# relaissteuerung.net
KiCad netlist of a schematic drawn in EAGLE
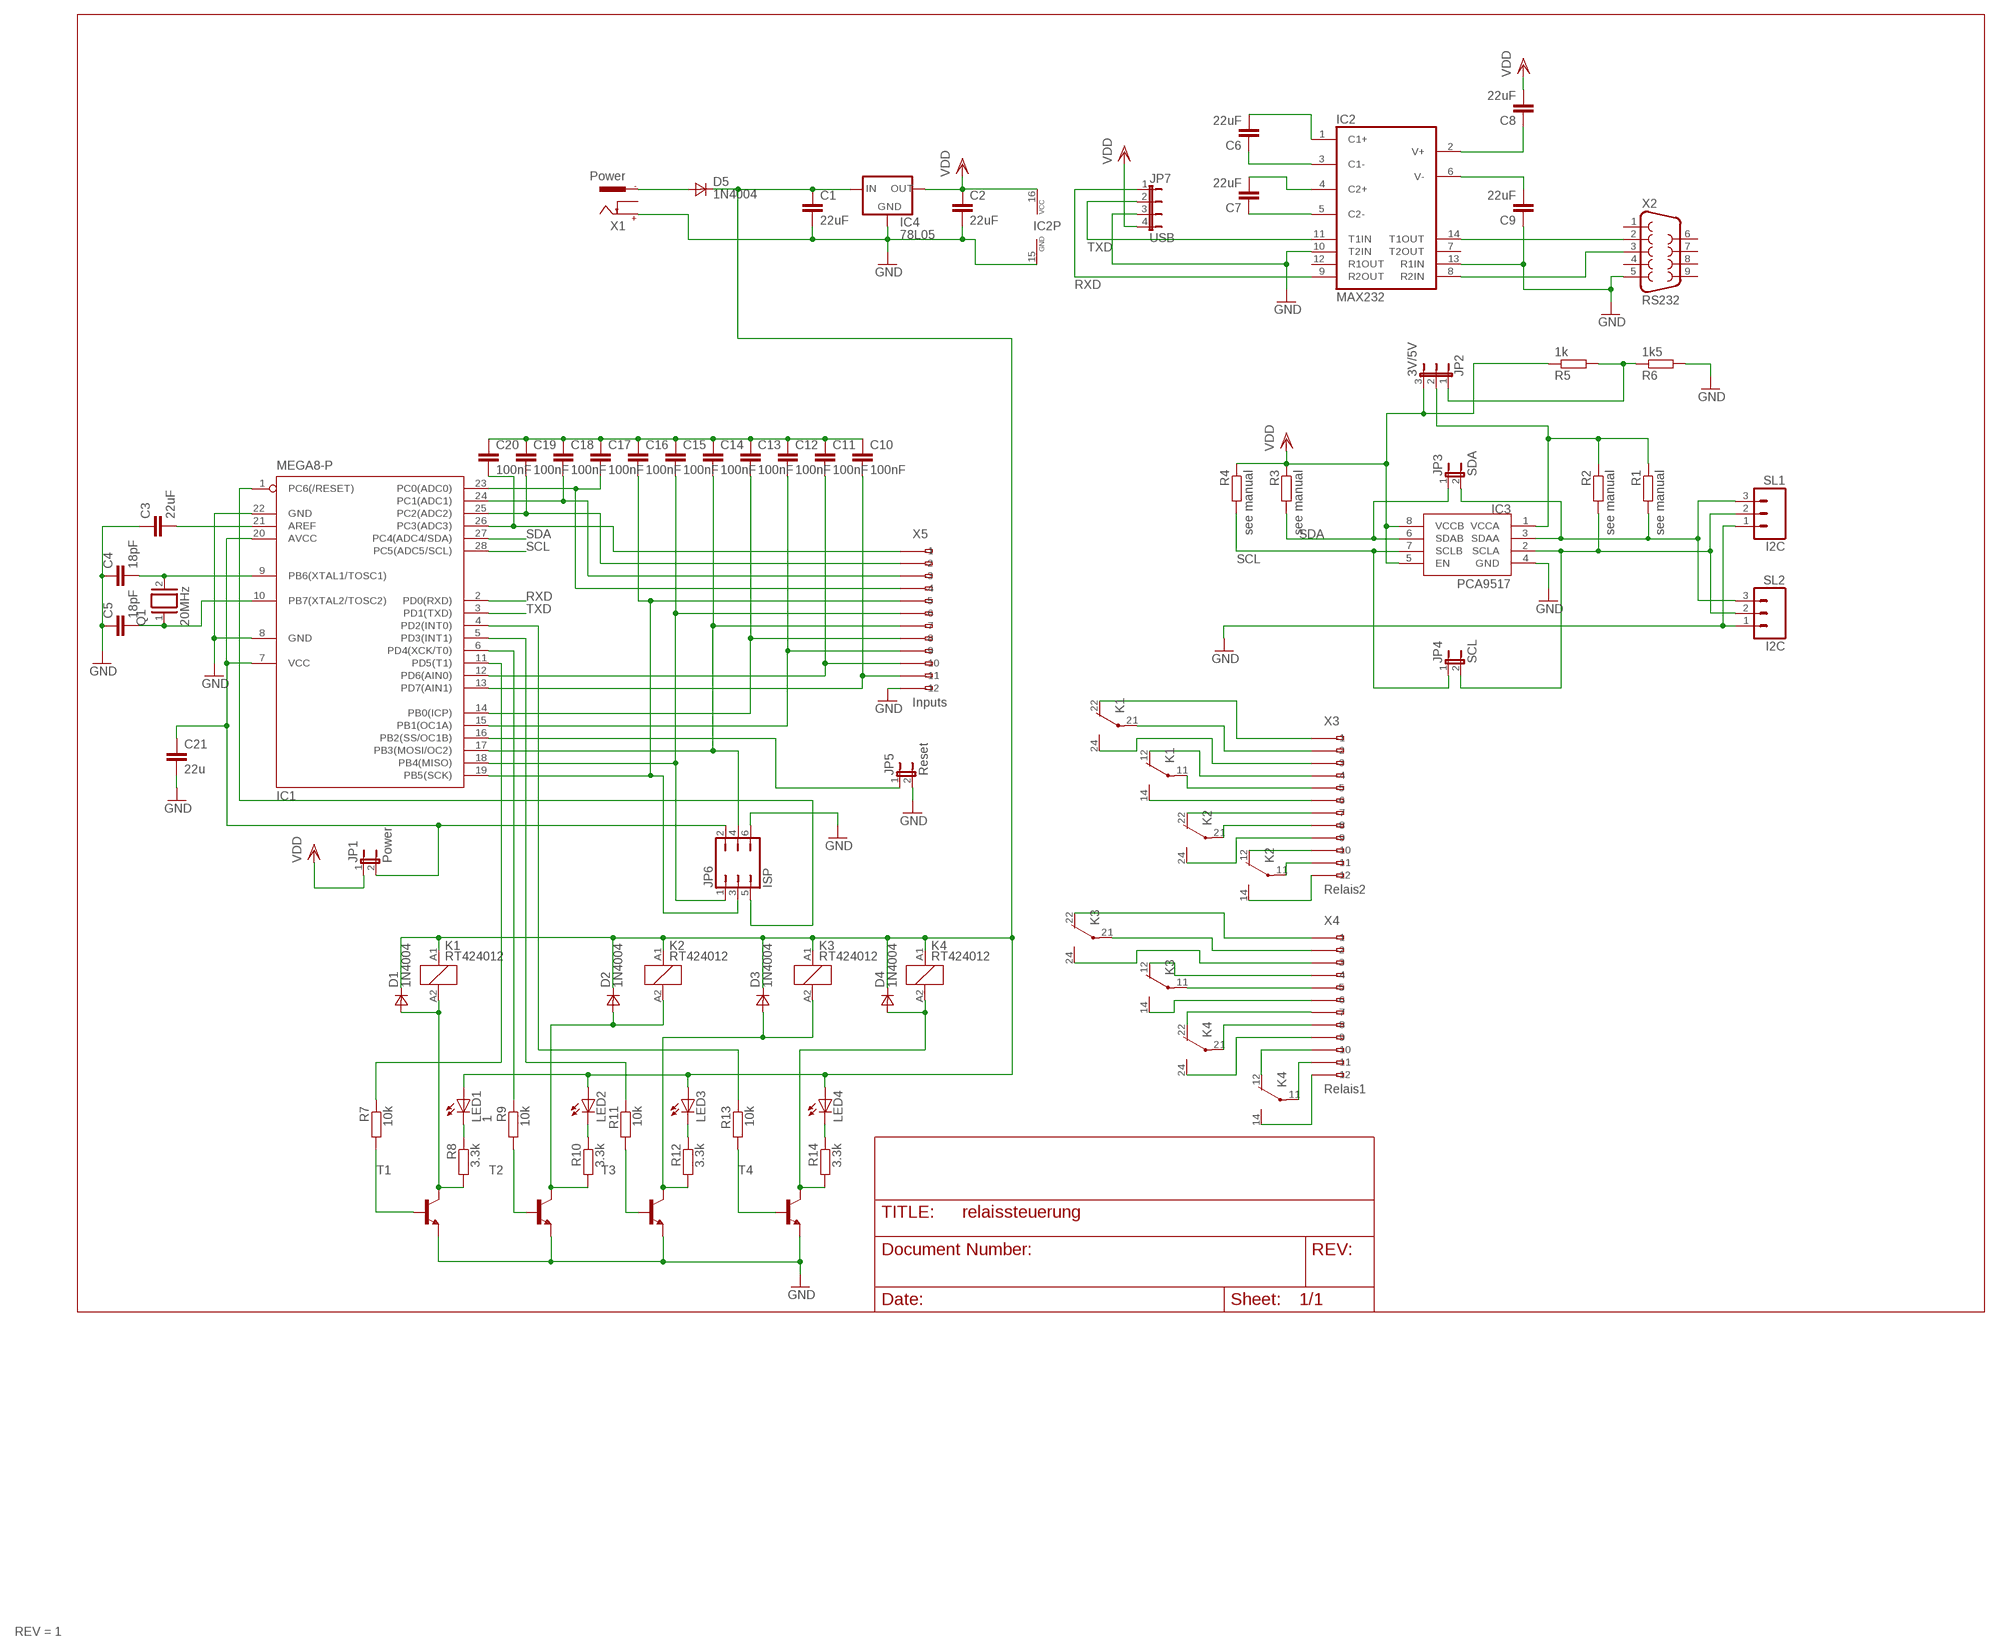
[diagram p0: schematic, sheet 1]

(export (version "E")
  (design (tool "Eeschema 10.0.6"))
  (components
    (comp (ref "C1")
      (value "22uF")
      (footprint "eagle-import:C1206")
      (libsource (lib "eagle-import") (part "resistor_C-EUC1206"))
    )
    (comp (ref "C2")
      (value "22uF")
      (footprint "eagle-import:C1206")
      (libsource (lib "eagle-import") (part "resistor_C-EUC1206"))
    )
    (comp (ref "C3")
      (value "22uF")
      (footprint "eagle-import:C1206")
      (libsource (lib "eagle-import") (part "resistor_C-EUC1206"))
    )
    (comp (ref "C4")
      (value "18pF")
      (footprint "eagle-import:C050-025X075")
      (libsource (lib "eagle-import") (part "resistor_C-EU050-025X075"))
    )
    (comp (ref "C5")
      (value "18pF")
      (footprint "eagle-import:C050-025X075")
      (libsource (lib "eagle-import") (part "resistor_C-EU050-025X075"))
    )
    (comp (ref "C6")
      (value "22uF")
      (footprint "eagle-import:C1206")
      (libsource (lib "eagle-import") (part "C-EUC1206"))
    )
    (comp (ref "C7")
      (value "22uF")
      (footprint "eagle-import:C1206")
      (libsource (lib "eagle-import") (part "C-EUC1206"))
    )
    (comp (ref "C8")
      (value "22uF")
      (footprint "eagle-import:C1206")
      (libsource (lib "eagle-import") (part "C-EUC1206"))
    )
    (comp (ref "C9")
      (value "22uF")
      (footprint "eagle-import:C1206")
      (libsource (lib "eagle-import") (part "C-EUC1206"))
    )
    (comp (ref "C10")
      (value "100nF")
      (footprint "eagle-import:C1206")
      (libsource (lib "eagle-import") (part "resistor_C-EUC1206"))
    )
    (comp (ref "C11")
      (value "100nF")
      (footprint "eagle-import:C1206")
      (libsource (lib "eagle-import") (part "resistor_C-EUC1206"))
    )
    (comp (ref "C12")
      (value "100nF")
      (footprint "eagle-import:C1206")
      (libsource (lib "eagle-import") (part "resistor_C-EUC1206"))
    )
    (comp (ref "C13")
      (value "100nF")
      (footprint "eagle-import:C1206")
      (libsource (lib "eagle-import") (part "resistor_C-EUC1206"))
    )
    (comp (ref "C14")
      (value "100nF")
      (footprint "eagle-import:C1206")
      (libsource (lib "eagle-import") (part "resistor_C-EUC1206"))
    )
    (comp (ref "C15")
      (value "100nF")
      (footprint "eagle-import:C1206")
      (libsource (lib "eagle-import") (part "resistor_C-EUC1206"))
    )
    (comp (ref "C16")
      (value "100nF")
      (footprint "eagle-import:C1206")
      (libsource (lib "eagle-import") (part "resistor_C-EUC1206"))
    )
    (comp (ref "C17")
      (value "100nF")
      (footprint "eagle-import:C1206")
      (libsource (lib "eagle-import") (part "resistor_C-EUC1206"))
    )
    (comp (ref "C18")
      (value "100nF")
      (footprint "eagle-import:C1206")
      (libsource (lib "eagle-import") (part "resistor_C-EUC1206"))
    )
    (comp (ref "C19")
      (value "100nF")
      (footprint "eagle-import:C1206")
      (libsource (lib "eagle-import") (part "resistor_C-EUC1206"))
    )
    (comp (ref "C20")
      (value "100nF")
      (footprint "eagle-import:C1206")
      (libsource (lib "eagle-import") (part "resistor_C-EUC1206"))
    )
    (comp (ref "C21")
      (value "22u")
      (footprint "eagle-import:C1206")
      (libsource (lib "eagle-import") (part "resistor_C-EUC1206"))
    )
    (comp (ref "D1")
      (value "1N4004")
      (footprint "eagle-import:E2LINE")
      (libsource (lib "eagle-import") (part "D_E2L"))
    )
    (comp (ref "D2")
      (value "1N4004")
      (footprint "eagle-import:E2LINE")
      (libsource (lib "eagle-import") (part "D_E2L"))
    )
    (comp (ref "D3")
      (value "1N4004")
      (footprint "eagle-import:E2LINE")
      (libsource (lib "eagle-import") (part "D_E2L"))
    )
    (comp (ref "D4")
      (value "1N4004")
      (footprint "eagle-import:E2LINE")
      (libsource (lib "eagle-import") (part "D_E2L"))
    )
    (comp (ref "D5")
      (value "1N4004")
      (footprint "eagle-import:E2LINE")
      (libsource (lib "eagle-import") (part "D_E2L"))
    )
    (comp (ref "IC1")
      (value "MEGA8-P")
      (footprint "eagle-import:DIL28-3")
      (libsource (lib "eagle-import") (part "MEGA8-P"))
    )
    (comp (ref "IC2")
      (value "MAX232")
      (footprint "eagle-import:DIL16")
      (fields (field (name "MF") "MAXIM") (field (name "MPN") "MAX232ACPE+"))
      (libsource (lib "eagle-import") (part "MAX232"))
    )
    (comp (ref "IC3")
      (value "PCA9517")
      (footprint "eagle-import:SO-08")
      (libsource (lib "eagle-import") (part "PCA9517"))
    )
    (comp (ref "IC4")
      (value "78L05")
      (footprint "eagle-import:78LXX")
      (libsource (lib "eagle-import") (part "78LXX"))
    )
    (comp (ref "JP1")
      (value "Power")
      (footprint "eagle-import:JP1")
      (libsource (lib "eagle-import") (part "JP1E"))
    )
    (comp (ref "JP2")
      (value "3V/5V")
      (footprint "eagle-import:JP2")
      (libsource (lib "eagle-import") (part "JP2E"))
    )
    (comp (ref "JP3")
      (value "SDA")
      (footprint "eagle-import:JP1")
      (libsource (lib "eagle-import") (part "JP1E"))
    )
    (comp (ref "JP4")
      (value "SCL")
      (footprint "eagle-import:JP1")
      (libsource (lib "eagle-import") (part "JP1E"))
    )
    (comp (ref "JP5")
      (value "Reset")
      (footprint "eagle-import:JP1")
      (libsource (lib "eagle-import") (part "JP1E"))
    )
    (comp (ref "JP6")
      (value "ISP")
      (footprint "eagle-import:JP3Q")
      (libsource (lib "eagle-import") (part "JP3Q"))
    )
    (comp (ref "JP7")
      (value "USB")
      (footprint "eagle-import:JP4")
      (libsource (lib "eagle-import") (part "JP4E"))
    )
    (comp (ref "K1")
      (value "RT424012")
      (footprint "eagle-import:RT2C_O")
      (libsource (lib "eagle-import") (part "RT42?4012"))
    )
    (comp (ref "K2")
      (value "RT424012")
      (footprint "eagle-import:RT2C_O")
      (libsource (lib "eagle-import") (part "RT42?4012"))
    )
    (comp (ref "K3")
      (value "RT424012")
      (footprint "eagle-import:RT2C_O")
      (libsource (lib "eagle-import") (part "RT42?4012"))
    )
    (comp (ref "K4")
      (value "RT424012")
      (footprint "eagle-import:RT2C_O")
      (libsource (lib "eagle-import") (part "RT42?4012"))
    )
    (comp (ref "LED1")
      (value "1")
      (footprint "eagle-import:LED3MM")
      (libsource (lib "eagle-import") (part "LED3MM"))
    )
    (comp (ref "LED2")
      (value "LED3MM")
      (footprint "eagle-import:LED3MM")
      (libsource (lib "eagle-import") (part "LED3MM"))
    )
    (comp (ref "LED3")
      (value "LED3MM")
      (footprint "eagle-import:LED3MM")
      (libsource (lib "eagle-import") (part "LED3MM"))
    )
    (comp (ref "LED4")
      (value "LED3MM")
      (footprint "eagle-import:LED3MM")
      (libsource (lib "eagle-import") (part "LED3MM"))
    )
    (comp (ref "Q1")
      (value "20MHz")
      (footprint "eagle-import:QS")
      (libsource (lib "eagle-import") (part "XTAL/S"))
    )
    (comp (ref "R1")
      (value "see manual")
      (footprint "eagle-import:R1206")
      (libsource (lib "eagle-import") (part "resistor_R-EU_R1206"))
    )
    (comp (ref "R2")
      (value "see manual")
      (footprint "eagle-import:R1206")
      (libsource (lib "eagle-import") (part "resistor_R-EU_R1206"))
    )
    (comp (ref "R3")
      (value "see manual")
      (footprint "eagle-import:R1206")
      (libsource (lib "eagle-import") (part "resistor_R-EU_R1206"))
    )
    (comp (ref "R4")
      (value "see manual")
      (footprint "eagle-import:R1206")
      (libsource (lib "eagle-import") (part "resistor_R-EU_R1206"))
    )
    (comp (ref "R5")
      (value "1k")
      (footprint "eagle-import:R1206")
      (libsource (lib "eagle-import") (part "resistor_R-EU_R1206"))
    )
    (comp (ref "R6")
      (value "1k5")
      (footprint "eagle-import:R1206")
      (libsource (lib "eagle-import") (part "resistor_R-EU_R1206"))
    )
    (comp (ref "R7")
      (value "10k")
      (footprint "eagle-import:R1206")
      (libsource (lib "eagle-import") (part "R-EU_R1206"))
    )
    (comp (ref "R8")
      (value "3.3k")
      (footprint "eagle-import:R1206")
      (libsource (lib "eagle-import") (part "R-EU_R1206"))
    )
    (comp (ref "R9")
      (value "10k")
      (footprint "eagle-import:M1206")
      (libsource (lib "eagle-import") (part "R-EU_M1206"))
    )
    (comp (ref "R10")
      (value "3.3k")
      (footprint "eagle-import:R1206")
      (libsource (lib "eagle-import") (part "R-EU_R1206"))
    )
    (comp (ref "R11")
      (value "10k")
      (footprint "eagle-import:R1206")
      (libsource (lib "eagle-import") (part "R-EU_R1206"))
    )
    (comp (ref "R12")
      (value "3.3k")
      (footprint "eagle-import:R1206")
      (libsource (lib "eagle-import") (part "R-EU_R1206"))
    )
    (comp (ref "R13")
      (value "10k")
      (footprint "eagle-import:M1206")
      (libsource (lib "eagle-import") (part "R-EU_M1206"))
    )
    (comp (ref "R14")
      (value "3.3k")
      (footprint "eagle-import:R1206")
      (libsource (lib "eagle-import") (part "R-EU_R1206"))
    )
    (comp (ref "SL1")
      (value "I2C")
      (footprint "eagle-import:03P")
      (libsource (lib "eagle-import") (part "M03"))
    )
    (comp (ref "SL2")
      (value "I2C")
      (footprint "eagle-import:03P")
      (libsource (lib "eagle-import") (part "M03"))
    )
    (comp (ref "T1")
      (value "BC817-16-NPN-SOT23-BEC")
      (footprint "eagle-import:SOT23-BEC")
      (libsource (lib "eagle-import") (part "-NPN-SOT23-BECBC817-16"))
    )
    (comp (ref "T2")
      (value "BC817-16-NPN-SOT23-BEC")
      (footprint "eagle-import:SOT23-BEC")
      (libsource (lib "eagle-import") (part "-NPN-SOT23-BECBC817-16"))
    )
    (comp (ref "T3")
      (value "BC817-16-NPN-SOT23-BEC")
      (footprint "eagle-import:SOT23-BEC")
      (libsource (lib "eagle-import") (part "-NPN-SOT23-BECBC817-16"))
    )
    (comp (ref "T4")
      (value "BC817-16-NPN-SOT23-BEC")
      (footprint "eagle-import:SOT23-BEC")
      (libsource (lib "eagle-import") (part "-NPN-SOT23-BECBC817-16"))
    )
    (comp (ref "X1")
      (value "Power")
      (footprint "eagle-import:737992-5")
      (libsource (lib "eagle-import") (part "737992-55"))
    )
    (comp (ref "X2")
      (value "RS232")
      (footprint "eagle-import:F09H")
      (libsource (lib "eagle-import") (part "F09H"))
    )
    (comp (ref "X3")
      (value "Relais2")
      (footprint "eagle-import:233-512")
      (fields (field (name "MF") "Wago Corporation") (field (name "MPN") "0233-0512"))
      (libsource (lib "eagle-import") (part "233-512"))
    )
    (comp (ref "X4")
      (value "Relais1")
      (footprint "eagle-import:233-512")
      (fields (field (name "MF") "Wago Corporation") (field (name "MPN") "0233-0512"))
      (libsource (lib "eagle-import") (part "233-512"))
    )
    (comp (ref "X5")
      (value "Inputs")
      (footprint "eagle-import:233-512")
      (fields (field (name "MF") "Wago Corporation") (field (name "MPN") "0233-0512"))
      (libsource (lib "eagle-import") (part "233-512"))
    )
  )
  (nets
    (net (code "1") (name "/RXD") (class "Default")
      (node (ref "IC1") (pin "2") (pinfunction "PD0(RXD)_2") (pintype "bidirectional"))
      (node (ref "IC2") (pin "9") (pinfunction "R2OUT_9") (pintype "output"))
      (node (ref "JP7") (pin "1") (pinfunction "1_1") (pintype "passive"))
    )
    (net (code "2") (name "/SCL") (class "Default")
      (node (ref "IC1") (pin "28") (pinfunction "PC5(ADC5/SCL)_28") (pintype "bidirectional"))
      (node (ref "IC3") (pin "7") (pinfunction "SCLB_7") (pintype "bidirectional"))
      (node (ref "JP4") (pin "1") (pinfunction "1_1") (pintype "passive"))
      (node (ref "R4") (pin "2") (pinfunction "2_2") (pintype "passive"))
    )
    (net (code "3") (name "/SDA") (class "Default")
      (node (ref "IC1") (pin "27") (pinfunction "PC4(ADC4/SDA)_27") (pintype "bidirectional"))
      (node (ref "IC3") (pin "6") (pinfunction "SDAB_6") (pintype "bidirectional"))
      (node (ref "JP3") (pin "1") (pinfunction "1_1") (pintype "passive"))
      (node (ref "R3") (pin "2") (pinfunction "2_2") (pintype "passive"))
    )
    (net (code "4") (name "/TXD") (class "Default")
      (node (ref "IC1") (pin "3") (pinfunction "PD1(TXD)_3") (pintype "bidirectional"))
      (node (ref "IC2") (pin "11") (pinfunction "T1IN_11") (pintype "input"))
      (node (ref "JP7") (pin "2") (pinfunction "2_2") (pintype "passive"))
    )
    (net (code "5") (name "GND") (class "Default")
      (node (ref "C1") (pin "2") (pinfunction "2_2") (pintype "passive"))
      (node (ref "C2") (pin "2") (pinfunction "2_2") (pintype "passive"))
      (node (ref "C21") (pin "2") (pinfunction "2_2") (pintype "passive"))
      (node (ref "C3") (pin "1") (pinfunction "1_1") (pintype "passive"))
      (node (ref "C4") (pin "1") (pinfunction "1_1") (pintype "passive"))
      (node (ref "C5") (pin "1") (pinfunction "1_1") (pintype "passive"))
      (node (ref "C9") (pin "1") (pinfunction "1_1") (pintype "passive"))
      (node (ref "IC1") (pin "22") (pinfunction "GND_22") (pintype "power_in"))
      (node (ref "IC1") (pin "8") (pinfunction "GND_8") (pintype "power_in"))
      (node (ref "IC2") (pin "10") (pinfunction "T2IN_10") (pintype "input"))
      (node (ref "IC2") (pin "13") (pinfunction "R1IN_13") (pintype "input"))
      (node (ref "IC2") (pin "15") (pinfunction "GND_15") (pintype "power_in"))
      (node (ref "IC3") (pin "4") (pinfunction "GND_4") (pintype "bidirectional"))
      (node (ref "IC4") (pin "GND") (pinfunction "GND_GND") (pintype "input"))
      (node (ref "JP5") (pin "2") (pinfunction "2_2") (pintype "passive"))
      (node (ref "JP6") (pin "6") (pinfunction "6_6") (pintype "passive"))
      (node (ref "JP7") (pin "3") (pinfunction "3_3") (pintype "passive"))
      (node (ref "R6") (pin "2") (pinfunction "2_2") (pintype "passive"))
      (node (ref "SL1") (pin "1") (pinfunction "1_1") (pintype "passive"))
      (node (ref "SL2") (pin "1") (pinfunction "1_1") (pintype "passive"))
      (node (ref "T1") (pin "E") (pinfunction "E_E") (pintype "passive"))
      (node (ref "T2") (pin "E") (pinfunction "E_E") (pintype "passive"))
      (node (ref "T3") (pin "E") (pinfunction "E_E") (pintype "passive"))
      (node (ref "T4") (pin "E") (pinfunction "E_E") (pintype "passive"))
      (node (ref "X1") (pin "+") (pinfunction "+_+") (pintype "passive"))
      (node (ref "X2") (pin "5") (pinfunction "5_5") (pintype "passive"))
      (node (ref "X5") (pin "A12") (pinfunction "-12_A12") (pintype "passive"))
    )
    (net (code "6") (name "Net-(C10-Pad1)") (class "Default")
      (node (ref "C10") (pin "1") (pinfunction "1_1") (pintype "passive"))
      (node (ref "C11") (pin "1") (pinfunction "1_1") (pintype "passive"))
      (node (ref "C12") (pin "1") (pinfunction "1_1") (pintype "passive"))
      (node (ref "C13") (pin "1") (pinfunction "1_1") (pintype "passive"))
      (node (ref "C14") (pin "1") (pinfunction "1_1") (pintype "passive"))
      (node (ref "C15") (pin "1") (pinfunction "1_1") (pintype "passive"))
      (node (ref "C16") (pin "1") (pinfunction "1_1") (pintype "passive"))
      (node (ref "C17") (pin "1") (pinfunction "1_1") (pintype "passive"))
      (node (ref "C18") (pin "1") (pinfunction "1_1") (pintype "passive"))
      (node (ref "C19") (pin "1") (pinfunction "1_1") (pintype "passive"))
      (node (ref "C20") (pin "1") (pinfunction "1_1") (pintype "passive"))
    )
    (net (code "7") (name "Net-(D1-A)") (class "Default")
      (node (ref "D1") (pin "2") (pinfunction "A_2") (pintype "passive"))
      (node (ref "K1") (pin "A2") (pinfunction "2_A2") (pintype "passive"))
      (node (ref "R8") (pin "2") (pinfunction "2_2") (pintype "passive"))
      (node (ref "T1") (pin "C") (pinfunction "C_C") (pintype "passive"))
    )
    (net (code "8") (name "Net-(D1-C)") (class "Default")
      (node (ref "C1") (pin "1") (pinfunction "1_1") (pintype "passive"))
      (node (ref "D1") (pin "1") (pinfunction "C_1") (pintype "passive"))
      (node (ref "D2") (pin "1") (pinfunction "C_1") (pintype "passive"))
      (node (ref "D3") (pin "1") (pinfunction "C_1") (pintype "passive"))
      (node (ref "D4") (pin "1") (pinfunction "C_1") (pintype "passive"))
      (node (ref "D5") (pin "1") (pinfunction "C_1") (pintype "passive"))
      (node (ref "IC4") (pin "IN") (pinfunction "IN_IN") (pintype "input"))
      (node (ref "K1") (pin "A1") (pinfunction "1_A1") (pintype "passive"))
      (node (ref "K2") (pin "A1") (pinfunction "1_A1") (pintype "passive"))
      (node (ref "K3") (pin "A1") (pinfunction "1_A1") (pintype "passive"))
      (node (ref "K4") (pin "A1") (pinfunction "1_A1") (pintype "passive"))
      (node (ref "LED1") (pin "A") (pinfunction "A_A") (pintype "passive"))
      (node (ref "LED2") (pin "A") (pinfunction "A_A") (pintype "passive"))
      (node (ref "LED3") (pin "A") (pinfunction "A_A") (pintype "passive"))
      (node (ref "LED4") (pin "A") (pinfunction "A_A") (pintype "passive"))
    )
    (net (code "9") (name "Net-(D2-A)") (class "Default")
      (node (ref "D2") (pin "2") (pinfunction "A_2") (pintype "passive"))
      (node (ref "K2") (pin "A2") (pinfunction "2_A2") (pintype "passive"))
      (node (ref "R10") (pin "2") (pinfunction "2_2") (pintype "passive"))
      (node (ref "T2") (pin "C") (pinfunction "C_C") (pintype "passive"))
    )
    (net (code "10") (name "Net-(D3-A)") (class "Default")
      (node (ref "D3") (pin "2") (pinfunction "A_2") (pintype "passive"))
      (node (ref "K3") (pin "A2") (pinfunction "2_A2") (pintype "passive"))
      (node (ref "R12") (pin "2") (pinfunction "2_2") (pintype "passive"))
      (node (ref "T3") (pin "C") (pinfunction "C_C") (pintype "passive"))
    )
    (net (code "11") (name "Net-(D4-A)") (class "Default")
      (node (ref "D4") (pin "2") (pinfunction "A_2") (pintype "passive"))
      (node (ref "K4") (pin "A2") (pinfunction "2_A2") (pintype "passive"))
      (node (ref "R14") (pin "2") (pinfunction "2_2") (pintype "passive"))
      (node (ref "T4") (pin "C") (pinfunction "C_C") (pintype "passive"))
    )
    (net (code "12") (name "Net-(D5-A)") (class "Default")
      (node (ref "D5") (pin "2") (pinfunction "A_2") (pintype "passive"))
      (node (ref "X1") (pin "-1") (pinfunction "-1_-1") (pintype "passive"))
    )
    (net (code "13") (name "Net-(IC1-AREF)") (class "Default")
      (node (ref "C3") (pin "2") (pinfunction "2_2") (pintype "passive"))
      (node (ref "IC1") (pin "21") (pinfunction "AREF_21") (pintype "passive"))
    )
    (net (code "14") (name "Net-(IC1-AVCC)") (class "Default")
      (node (ref "C21") (pin "1") (pinfunction "1_1") (pintype "passive"))
      (node (ref "IC1") (pin "20") (pinfunction "AVCC_20") (pintype "power_in"))
      (node (ref "IC1") (pin "7") (pinfunction "VCC_7") (pintype "power_in"))
      (node (ref "JP1") (pin "2") (pinfunction "2_2") (pintype "passive"))
      (node (ref "JP6") (pin "2") (pinfunction "2_2") (pintype "passive"))
    )
    (net (code "15") (name "Net-(IC1-PB0(ICP))") (class "Default")
      (node (ref "C13") (pin "2") (pinfunction "2_2") (pintype "passive"))
      (node (ref "IC1") (pin "14") (pinfunction "PB0(ICP)_14") (pintype "bidirectional"))
      (node (ref "X5") (pin "A8") (pinfunction "-8_A8") (pintype "passive"))
    )
    (net (code "16") (name "Net-(IC1-PB1(OC1A))") (class "Default")
      (node (ref "C12") (pin "2") (pinfunction "2_2") (pintype "passive"))
      (node (ref "IC1") (pin "15") (pinfunction "PB1(OC1A)_15") (pintype "bidirectional"))
      (node (ref "X5") (pin "A9") (pinfunction "-9_A9") (pintype "passive"))
    )
    (net (code "17") (name "Net-(IC1-PB2(SS{slash}OC1B))") (class "Default")
      (node (ref "IC1") (pin "16") (pinfunction "PB2(SS/OC1B)_16") (pintype "bidirectional"))
      (node (ref "JP5") (pin "1") (pinfunction "1_1") (pintype "passive"))
    )
    (net (code "18") (name "Net-(IC1-PB3(MOSI{slash}OC2))") (class "Default")
      (node (ref "C14") (pin "2") (pinfunction "2_2") (pintype "passive"))
      (node (ref "IC1") (pin "17") (pinfunction "PB3(MOSI/OC2)_17") (pintype "bidirectional"))
      (node (ref "JP6") (pin "4") (pinfunction "4_4") (pintype "passive"))
      (node (ref "X5") (pin "A7") (pinfunction "-7_A7") (pintype "passive"))
    )
    (net (code "19") (name "Net-(IC1-PB4(MISO))") (class "Default")
      (node (ref "C15") (pin "2") (pinfunction "2_2") (pintype "passive"))
      (node (ref "IC1") (pin "18") (pinfunction "PB4(MISO)_18") (pintype "bidirectional"))
      (node (ref "JP6") (pin "1") (pinfunction "1_1") (pintype "passive"))
      (node (ref "X5") (pin "A6") (pinfunction "-6_A6") (pintype "passive"))
    )
    (net (code "20") (name "Net-(IC1-PB5(SCK))") (class "Default")
      (node (ref "C16") (pin "2") (pinfunction "2_2") (pintype "passive"))
      (node (ref "IC1") (pin "19") (pinfunction "PB5(SCK)_19") (pintype "bidirectional"))
      (node (ref "JP6") (pin "3") (pinfunction "3_3") (pintype "passive"))
      (node (ref "X5") (pin "A5") (pinfunction "-5_A5") (pintype "passive"))
    )
    (net (code "21") (name "Net-(IC1-PB6(XTAL1{slash}TOSC1))") (class "Default")
      (node (ref "C4") (pin "2") (pinfunction "2_2") (pintype "passive"))
      (node (ref "IC1") (pin "9") (pinfunction "PB6(XTAL1/TOSC1)_9") (pintype "bidirectional"))
      (node (ref "Q1") (pin "2") (pinfunction "2_2") (pintype "passive"))
    )
    (net (code "22") (name "Net-(IC1-PB7(XTAL2{slash}TOSC2))") (class "Default")
      (node (ref "C5") (pin "2") (pinfunction "2_2") (pintype "passive"))
      (node (ref "IC1") (pin "10") (pinfunction "PB7(XTAL2/TOSC2)_10") (pintype "bidirectional"))
      (node (ref "Q1") (pin "1") (pinfunction "1_1") (pintype "passive"))
    )
    (net (code "23") (name "Net-(IC1-PC0(ADC0))") (class "Default")
      (node (ref "C17") (pin "2") (pinfunction "2_2") (pintype "passive"))
      (node (ref "IC1") (pin "23") (pinfunction "PC0(ADC0)_23") (pintype "bidirectional"))
      (node (ref "X5") (pin "A4") (pinfunction "-4_A4") (pintype "passive"))
    )
    (net (code "24") (name "Net-(IC1-PC1(ADC1))") (class "Default")
      (node (ref "C18") (pin "2") (pinfunction "2_2") (pintype "passive"))
      (node (ref "IC1") (pin "24") (pinfunction "PC1(ADC1)_24") (pintype "bidirectional"))
      (node (ref "X5") (pin "A3") (pinfunction "-3_A3") (pintype "passive"))
    )
    (net (code "25") (name "Net-(IC1-PC2(ADC2))") (class "Default")
      (node (ref "C19") (pin "2") (pinfunction "2_2") (pintype "passive"))
      (node (ref "IC1") (pin "25") (pinfunction "PC2(ADC2)_25") (pintype "bidirectional"))
      (node (ref "X5") (pin "A2") (pinfunction "-2_A2") (pintype "passive"))
    )
    (net (code "26") (name "Net-(IC1-PC3(ADC3))") (class "Default")
      (node (ref "C20") (pin "2") (pinfunction "2_2") (pintype "passive"))
      (node (ref "IC1") (pin "26") (pinfunction "PC3(ADC3)_26") (pintype "bidirectional"))
      (node (ref "X5") (pin "A1") (pinfunction "-1_A1") (pintype "passive"))
    )
    (net (code "27") (name "Net-(IC1-PC6({slash}RESET))") (class "Default")
      (node (ref "IC1") (pin "1") (pinfunction "PC6(/RESET)_1") (pintype "bidirectional"))
      (node (ref "JP6") (pin "5") (pinfunction "5_5") (pintype "passive"))
    )
    (net (code "28") (name "Net-(IC1-PD2(INT0))") (class "Default")
      (node (ref "IC1") (pin "4") (pinfunction "PD2(INT0)_4") (pintype "bidirectional"))
      (node (ref "R13") (pin "1") (pinfunction "1_1") (pintype "passive"))
    )
    (net (code "29") (name "Net-(IC1-PD3(INT1))") (class "Default")
      (node (ref "IC1") (pin "5") (pinfunction "PD3(INT1)_5") (pintype "bidirectional"))
      (node (ref "R11") (pin "1") (pinfunction "1_1") (pintype "passive"))
    )
    (net (code "30") (name "Net-(IC1-PD4(XCK{slash}T0))") (class "Default")
      (node (ref "IC1") (pin "6") (pinfunction "PD4(XCK/T0)_6") (pintype "bidirectional"))
      (node (ref "R9") (pin "1") (pinfunction "1_1") (pintype "passive"))
    )
    (net (code "31") (name "Net-(IC1-PD5(T1))") (class "Default")
      (node (ref "IC1") (pin "11") (pinfunction "PD5(T1)_11") (pintype "bidirectional"))
      (node (ref "R7") (pin "1") (pinfunction "1_1") (pintype "passive"))
    )
    (net (code "32") (name "Net-(IC1-PD6(AIN0))") (class "Default")
      (node (ref "C11") (pin "2") (pinfunction "2_2") (pintype "passive"))
      (node (ref "IC1") (pin "12") (pinfunction "PD6(AIN0)_12") (pintype "bidirectional"))
      (node (ref "X5") (pin "A10") (pinfunction "-10_A10") (pintype "passive"))
    )
    (net (code "33") (name "Net-(IC1-PD7(AIN1))") (class "Default")
      (node (ref "C10") (pin "2") (pinfunction "2_2") (pintype "passive"))
      (node (ref "IC1") (pin "13") (pinfunction "PD7(AIN1)_13") (pintype "bidirectional"))
      (node (ref "X5") (pin "A11") (pinfunction "-11_A11") (pintype "passive"))
    )
    (net (code "34") (name "Net-(IC2A-C1+)") (class "Default")
      (node (ref "C6") (pin "2") (pinfunction "2_2") (pintype "passive"))
      (node (ref "IC2") (pin "1") (pinfunction "C1+_1") (pintype "bidirectional"))
    )
    (net (code "35") (name "Net-(IC2A-C1-)") (class "Default")
      (node (ref "C6") (pin "1") (pinfunction "1_1") (pintype "passive"))
      (node (ref "IC2") (pin "3") (pinfunction "C1-_3") (pintype "bidirectional"))
    )
    (net (code "36") (name "Net-(IC2A-C2+)") (class "Default")
      (node (ref "C7") (pin "2") (pinfunction "2_2") (pintype "passive"))
      (node (ref "IC2") (pin "4") (pinfunction "C2+_4") (pintype "bidirectional"))
    )
    (net (code "37") (name "Net-(IC2A-C2-)") (class "Default")
      (node (ref "C7") (pin "1") (pinfunction "1_1") (pintype "passive"))
      (node (ref "IC2") (pin "5") (pinfunction "C2-_5") (pintype "bidirectional"))
    )
    (net (code "38") (name "Net-(IC2A-R2IN)") (class "Default")
      (node (ref "IC2") (pin "8") (pinfunction "R2IN_8") (pintype "input"))
      (node (ref "X2") (pin "3") (pinfunction "3_3") (pintype "passive"))
    )
    (net (code "39") (name "Net-(IC2A-T1OUT)") (class "Default")
      (node (ref "IC2") (pin "14") (pinfunction "T1OUT_14") (pintype "output"))
      (node (ref "X2") (pin "2") (pinfunction "2_2") (pintype "passive"))
    )
    (net (code "40") (name "Net-(IC2A-V+)") (class "Default")
      (node (ref "C8") (pin "1") (pinfunction "1_1") (pintype "passive"))
      (node (ref "IC2") (pin "2") (pinfunction "V+_2") (pintype "bidirectional"))
    )
    (net (code "41") (name "Net-(IC2A-V-)") (class "Default")
      (node (ref "C9") (pin "2") (pinfunction "2_2") (pintype "passive"))
      (node (ref "IC2") (pin "6") (pinfunction "V-_6") (pintype "bidirectional"))
    )
    (net (code "42") (name "Net-(IC3-SCLA)") (class "Default")
      (node (ref "IC3") (pin "2") (pinfunction "SCLA_2") (pintype "bidirectional"))
      (node (ref "JP4") (pin "2") (pinfunction "2_2") (pintype "passive"))
      (node (ref "R2") (pin "2") (pinfunction "2_2") (pintype "passive"))
      (node (ref "SL1") (pin "2") (pinfunction "2_2") (pintype "passive"))
      (node (ref "SL2") (pin "2") (pinfunction "2_2") (pintype "passive"))
    )
    (net (code "43") (name "Net-(IC3-SDAA)") (class "Default")
      (node (ref "IC3") (pin "3") (pinfunction "SDAA_3") (pintype "bidirectional"))
      (node (ref "JP3") (pin "2") (pinfunction "2_2") (pintype "passive"))
      (node (ref "R1") (pin "2") (pinfunction "2_2") (pintype "passive"))
      (node (ref "SL1") (pin "3") (pinfunction "3_3") (pintype "passive"))
      (node (ref "SL2") (pin "3") (pinfunction "3_3") (pintype "passive"))
    )
    (net (code "44") (name "Net-(IC3-VCCA)") (class "Default")
      (node (ref "IC3") (pin "1") (pinfunction "VCCA_1") (pintype "bidirectional"))
      (node (ref "JP2") (pin "2") (pinfunction "2_2") (pintype "passive"))
      (node (ref "R1") (pin "1") (pinfunction "1_1") (pintype "passive"))
      (node (ref "R2") (pin "1") (pinfunction "1_1") (pintype "passive"))
    )
    (net (code "45") (name "Net-(JP2-Pad1)") (class "Default")
      (node (ref "JP2") (pin "1") (pinfunction "1_1") (pintype "passive"))
      (node (ref "R5") (pin "2") (pinfunction "2_2") (pintype "passive"))
      (node (ref "R6") (pin "1") (pinfunction "1_1") (pintype "passive"))
    )
    (net (code "46") (name "Net-(K1B-O)") (class "Default")
      (node (ref "K1") (pin "12") (pinfunction "O_12") (pintype "passive"))
      (node (ref "X3") (pin "A4") (pinfunction "-4_A4") (pintype "passive"))
    )
    (net (code "47") (name "Net-(K1B-P)") (class "Default")
      (node (ref "K1") (pin "11") (pinfunction "P_11") (pintype "passive"))
      (node (ref "X3") (pin "A5") (pinfunction "-5_A5") (pintype "passive"))
    )
    (net (code "48") (name "Net-(K1B-S)") (class "Default")
      (node (ref "K1") (pin "14") (pinfunction "S_14") (pintype "passive"))
      (node (ref "X3") (pin "A6") (pinfunction "-6_A6") (pintype "passive"))
    )
    (net (code "49") (name "Net-(K1C-O)") (class "Default")
      (node (ref "K1") (pin "22") (pinfunction "O_22") (pintype "passive"))
      (node (ref "X3") (pin "A1") (pinfunction "-1_A1") (pintype "passive"))
    )
    (net (code "50") (name "Net-(K1C-P)") (class "Default")
      (node (ref "K1") (pin "21") (pinfunction "P_21") (pintype "passive"))
      (node (ref "X3") (pin "A2") (pinfunction "-2_A2") (pintype "passive"))
    )
    (net (code "51") (name "Net-(K1C-S)") (class "Default")
      (node (ref "K1") (pin "24") (pinfunction "S_24") (pintype "passive"))
      (node (ref "X3") (pin "A3") (pinfunction "-3_A3") (pintype "passive"))
    )
    (net (code "52") (name "Net-(K2B-O)") (class "Default")
      (node (ref "K2") (pin "12") (pinfunction "O_12") (pintype "passive"))
      (node (ref "X3") (pin "A10") (pinfunction "-10_A10") (pintype "passive"))
    )
    (net (code "53") (name "Net-(K2B-P)") (class "Default")
      (node (ref "K2") (pin "11") (pinfunction "P_11") (pintype "passive"))
      (node (ref "X3") (pin "A11") (pinfunction "-11_A11") (pintype "passive"))
    )
    (net (code "54") (name "Net-(K2B-S)") (class "Default")
      (node (ref "K2") (pin "14") (pinfunction "S_14") (pintype "passive"))
      (node (ref "X3") (pin "A12") (pinfunction "-12_A12") (pintype "passive"))
    )
    (net (code "55") (name "Net-(K2C-O)") (class "Default")
      (node (ref "K2") (pin "22") (pinfunction "O_22") (pintype "passive"))
      (node (ref "X3") (pin "A7") (pinfunction "-7_A7") (pintype "passive"))
    )
    (net (code "56") (name "Net-(K2C-P)") (class "Default")
      (node (ref "K2") (pin "21") (pinfunction "P_21") (pintype "passive"))
      (node (ref "X3") (pin "A8") (pinfunction "-8_A8") (pintype "passive"))
    )
    (net (code "57") (name "Net-(K2C-S)") (class "Default")
      (node (ref "K2") (pin "24") (pinfunction "S_24") (pintype "passive"))
      (node (ref "X3") (pin "A9") (pinfunction "-9_A9") (pintype "passive"))
    )
    (net (code "58") (name "Net-(K3B-O)") (class "Default")
      (node (ref "K3") (pin "12") (pinfunction "O_12") (pintype "passive"))
      (node (ref "X4") (pin "A4") (pinfunction "-4_A4") (pintype "passive"))
    )
    (net (code "59") (name "Net-(K3B-P)") (class "Default")
      (node (ref "K3") (pin "11") (pinfunction "P_11") (pintype "passive"))
      (node (ref "X4") (pin "A5") (pinfunction "-5_A5") (pintype "passive"))
    )
    (net (code "60") (name "Net-(K3B-S)") (class "Default")
      (node (ref "K3") (pin "14") (pinfunction "S_14") (pintype "passive"))
      (node (ref "X4") (pin "A6") (pinfunction "-6_A6") (pintype "passive"))
    )
    (net (code "61") (name "Net-(K3C-O)") (class "Default")
      (node (ref "K3") (pin "22") (pinfunction "O_22") (pintype "passive"))
      (node (ref "X4") (pin "A1") (pinfunction "-1_A1") (pintype "passive"))
    )
    (net (code "62") (name "Net-(K3C-P)") (class "Default")
      (node (ref "K3") (pin "21") (pinfunction "P_21") (pintype "passive"))
      (node (ref "X4") (pin "A2") (pinfunction "-2_A2") (pintype "passive"))
    )
    (net (code "63") (name "Net-(K3C-S)") (class "Default")
      (node (ref "K3") (pin "24") (pinfunction "S_24") (pintype "passive"))
      (node (ref "X4") (pin "A3") (pinfunction "-3_A3") (pintype "passive"))
    )
    (net (code "64") (name "Net-(K4B-O)") (class "Default")
      (node (ref "K4") (pin "12") (pinfunction "O_12") (pintype "passive"))
      (node (ref "X4") (pin "A10") (pinfunction "-10_A10") (pintype "passive"))
    )
    (net (code "65") (name "Net-(K4B-P)") (class "Default")
      (node (ref "K4") (pin "11") (pinfunction "P_11") (pintype "passive"))
      (node (ref "X4") (pin "A11") (pinfunction "-11_A11") (pintype "passive"))
    )
    (net (code "66") (name "Net-(K4B-S)") (class "Default")
      (node (ref "K4") (pin "14") (pinfunction "S_14") (pintype "passive"))
      (node (ref "X4") (pin "A12") (pinfunction "-12_A12") (pintype "passive"))
    )
    (net (code "67") (name "Net-(K4C-O)") (class "Default")
      (node (ref "K4") (pin "22") (pinfunction "O_22") (pintype "passive"))
      (node (ref "X4") (pin "A7") (pinfunction "-7_A7") (pintype "passive"))
    )
    (net (code "68") (name "Net-(K4C-P)") (class "Default")
      (node (ref "K4") (pin "21") (pinfunction "P_21") (pintype "passive"))
      (node (ref "X4") (pin "A8") (pinfunction "-8_A8") (pintype "passive"))
    )
    (net (code "69") (name "Net-(K4C-S)") (class "Default")
      (node (ref "K4") (pin "24") (pinfunction "S_24") (pintype "passive"))
      (node (ref "X4") (pin "A9") (pinfunction "-9_A9") (pintype "passive"))
    )
    (net (code "70") (name "Net-(LED1-C)") (class "Default")
      (node (ref "LED1") (pin "K") (pinfunction "C_K") (pintype "passive"))
      (node (ref "R8") (pin "1") (pinfunction "1_1") (pintype "passive"))
    )
    (net (code "71") (name "Net-(LED2-C)") (class "Default")
      (node (ref "LED2") (pin "K") (pinfunction "C_K") (pintype "passive"))
      (node (ref "R10") (pin "1") (pinfunction "1_1") (pintype "passive"))
    )
    (net (code "72") (name "Net-(LED3-C)") (class "Default")
      (node (ref "LED3") (pin "K") (pinfunction "C_K") (pintype "passive"))
      (node (ref "R12") (pin "1") (pinfunction "1_1") (pintype "passive"))
    )
    (net (code "73") (name "Net-(LED4-C)") (class "Default")
      (node (ref "LED4") (pin "K") (pinfunction "C_K") (pintype "passive"))
      (node (ref "R14") (pin "1") (pinfunction "1_1") (pintype "passive"))
    )
    (net (code "74") (name "Net-(R7-Pad2)") (class "Default")
      (node (ref "R7") (pin "2") (pinfunction "2_2") (pintype "passive"))
      (node (ref "T1") (pin "B") (pinfunction "B_B") (pintype "passive"))
    )
    (net (code "75") (name "Net-(R9-Pad2)") (class "Default")
      (node (ref "R9") (pin "2") (pinfunction "2_2") (pintype "passive"))
      (node (ref "T2") (pin "B") (pinfunction "B_B") (pintype "passive"))
    )
    (net (code "76") (name "Net-(R11-Pad2)") (class "Default")
      (node (ref "R11") (pin "2") (pinfunction "2_2") (pintype "passive"))
      (node (ref "T3") (pin "B") (pinfunction "B_B") (pintype "passive"))
    )
    (net (code "77") (name "Net-(R13-Pad2)") (class "Default")
      (node (ref "R13") (pin "2") (pinfunction "2_2") (pintype "passive"))
      (node (ref "T4") (pin "B") (pinfunction "B_B") (pintype "passive"))
    )
    (net (code "78") (name "VDD") (class "Default")
      (node (ref "C2") (pin "1") (pinfunction "1_1") (pintype "passive"))
      (node (ref "C8") (pin "2") (pinfunction "2_2") (pintype "passive"))
      (node (ref "IC2") (pin "16") (pinfunction "VCC_16") (pintype "power_in"))
      (node (ref "IC3") (pin "5") (pinfunction "EN_5") (pintype "bidirectional"))
      (node (ref "IC3") (pin "8") (pinfunction "VCCB_8") (pintype "bidirectional"))
      (node (ref "IC4") (pin "OUT") (pinfunction "OUT_OUT") (pintype "passive"))
      (node (ref "JP1") (pin "1") (pinfunction "1_1") (pintype "passive"))
      (node (ref "JP2") (pin "3") (pinfunction "3_3") (pintype "passive"))
      (node (ref "JP7") (pin "4") (pinfunction "4_4") (pintype "passive"))
      (node (ref "R3") (pin "1") (pinfunction "1_1") (pintype "passive"))
      (node (ref "R4") (pin "1") (pinfunction "1_1") (pintype "passive"))
      (node (ref "R5") (pin "1") (pinfunction "1_1") (pintype "passive"))
    )
    (net (code "79") (name "unconnected-(IC2A-R1OUT-Pad12)") (class "Default")
      (node (ref "IC2") (pin "12") (pinfunction "R1OUT_12") (pintype "output"))
    )
    (net (code "80") (name "unconnected-(IC2A-T2OUT-Pad7)") (class "Default")
      (node (ref "IC2") (pin "7") (pinfunction "T2OUT_7") (pintype "output"))
    )
    (net (code "81") (name "unconnected-(X1-Pad-2)") (class "Default")
      (node (ref "X1") (pin "-2") (pinfunction "-2_-2") (pintype "passive"))
    )
    (net (code "82") (name "unconnected-(X1-PadK)") (class "Default")
      (node (ref "X1") (pin "K") (pinfunction "K_K") (pintype "passive"))
    )
    (net (code "83") (name "unconnected-(X2-Pad1)") (class "Default")
      (node (ref "X2") (pin "1") (pinfunction "1_1") (pintype "passive"))
    )
    (net (code "84") (name "unconnected-(X2-Pad4)") (class "Default")
      (node (ref "X2") (pin "4") (pinfunction "4_4") (pintype "passive"))
    )
    (net (code "85") (name "unconnected-(X2-Pad6)") (class "Default")
      (node (ref "X2") (pin "6") (pinfunction "6_6") (pintype "passive"))
    )
    (net (code "86") (name "unconnected-(X2-Pad7)") (class "Default")
      (node (ref "X2") (pin "7") (pinfunction "7_7") (pintype "passive"))
    )
    (net (code "87") (name "unconnected-(X2-Pad8)") (class "Default")
      (node (ref "X2") (pin "8") (pinfunction "8_8") (pintype "passive"))
    )
    (net (code "88") (name "unconnected-(X2-Pad9)") (class "Default")
      (node (ref "X2") (pin "9") (pinfunction "9_9") (pintype "passive"))
    )
    (net (code "89") (name "unconnected-(X3-B-1-PadB1)") (class "Default")
      (node (ref "X3") (pin "B1") (pinfunction "B-1_B1") (pintype "passive"))
    )
    (net (code "90") (name "unconnected-(X3-B-2-PadB2)") (class "Default")
      (node (ref "X3") (pin "B2") (pinfunction "B-2_B2") (pintype "passive"))
    )
    (net (code "91") (name "unconnected-(X3-B-3-PadB3)") (class "Default")
      (node (ref "X3") (pin "B3") (pinfunction "B-3_B3") (pintype "passive"))
    )
    (net (code "92") (name "unconnected-(X3-B-4-PadB4)") (class "Default")
      (node (ref "X3") (pin "B4") (pinfunction "B-4_B4") (pintype "passive"))
    )
    (net (code "93") (name "unconnected-(X3-B-5-PadB5)") (class "Default")
      (node (ref "X3") (pin "B5") (pinfunction "B-5_B5") (pintype "passive"))
    )
    (net (code "94") (name "unconnected-(X3-B-6-PadB6)") (class "Default")
      (node (ref "X3") (pin "B6") (pinfunction "B-6_B6") (pintype "passive"))
    )
    (net (code "95") (name "unconnected-(X3-B-7-PadB7)") (class "Default")
      (node (ref "X3") (pin "B7") (pinfunction "B-7_B7") (pintype "passive"))
    )
    (net (code "96") (name "unconnected-(X3-B-8-PadB8)") (class "Default")
      (node (ref "X3") (pin "B8") (pinfunction "B-8_B8") (pintype "passive"))
    )
    (net (code "97") (name "unconnected-(X3-B-9-PadB9)") (class "Default")
      (node (ref "X3") (pin "B9") (pinfunction "B-9_B9") (pintype "passive"))
    )
    (net (code "98") (name "unconnected-(X3-B-10-PadB10)") (class "Default")
      (node (ref "X3") (pin "B10") (pinfunction "B-10_B10") (pintype "passive"))
    )
    (net (code "99") (name "unconnected-(X3-B-11-PadB11)") (class "Default")
      (node (ref "X3") (pin "B11") (pinfunction "B-11_B11") (pintype "passive"))
    )
    (net (code "100") (name "unconnected-(X3-B-12-PadB12)") (class "Default")
      (node (ref "X3") (pin "B12") (pinfunction "B-12_B12") (pintype "passive"))
    )
    (net (code "101") (name "unconnected-(X4-B-1-PadB1)") (class "Default")
      (node (ref "X4") (pin "B1") (pinfunction "B-1_B1") (pintype "passive"))
    )
    (net (code "102") (name "unconnected-(X4-B-2-PadB2)") (class "Default")
      (node (ref "X4") (pin "B2") (pinfunction "B-2_B2") (pintype "passive"))
    )
    (net (code "103") (name "unconnected-(X4-B-3-PadB3)") (class "Default")
      (node (ref "X4") (pin "B3") (pinfunction "B-3_B3") (pintype "passive"))
    )
    (net (code "104") (name "unconnected-(X4-B-4-PadB4)") (class "Default")
      (node (ref "X4") (pin "B4") (pinfunction "B-4_B4") (pintype "passive"))
    )
    (net (code "105") (name "unconnected-(X4-B-5-PadB5)") (class "Default")
      (node (ref "X4") (pin "B5") (pinfunction "B-5_B5") (pintype "passive"))
    )
    (net (code "106") (name "unconnected-(X4-B-6-PadB6)") (class "Default")
      (node (ref "X4") (pin "B6") (pinfunction "B-6_B6") (pintype "passive"))
    )
    (net (code "107") (name "unconnected-(X4-B-7-PadB7)") (class "Default")
      (node (ref "X4") (pin "B7") (pinfunction "B-7_B7") (pintype "passive"))
    )
    (net (code "108") (name "unconnected-(X4-B-8-PadB8)") (class "Default")
      (node (ref "X4") (pin "B8") (pinfunction "B-8_B8") (pintype "passive"))
    )
    (net (code "109") (name "unconnected-(X4-B-9-PadB9)") (class "Default")
      (node (ref "X4") (pin "B9") (pinfunction "B-9_B9") (pintype "passive"))
    )
    (net (code "110") (name "unconnected-(X4-B-10-PadB10)") (class "Default")
      (node (ref "X4") (pin "B10") (pinfunction "B-10_B10") (pintype "passive"))
    )
    (net (code "111") (name "unconnected-(X4-B-11-PadB11)") (class "Default")
      (node (ref "X4") (pin "B11") (pinfunction "B-11_B11") (pintype "passive"))
    )
    (net (code "112") (name "unconnected-(X4-B-12-PadB12)") (class "Default")
      (node (ref "X4") (pin "B12") (pinfunction "B-12_B12") (pintype "passive"))
    )
    (net (code "113") (name "unconnected-(X5-B-1-PadB1)") (class "Default")
      (node (ref "X5") (pin "B1") (pinfunction "B-1_B1") (pintype "passive"))
    )
    (net (code "114") (name "unconnected-(X5-B-2-PadB2)") (class "Default")
      (node (ref "X5") (pin "B2") (pinfunction "B-2_B2") (pintype "passive"))
    )
    (net (code "115") (name "unconnected-(X5-B-3-PadB3)") (class "Default")
      (node (ref "X5") (pin "B3") (pinfunction "B-3_B3") (pintype "passive"))
    )
    (net (code "116") (name "unconnected-(X5-B-4-PadB4)") (class "Default")
      (node (ref "X5") (pin "B4") (pinfunction "B-4_B4") (pintype "passive"))
    )
    (net (code "117") (name "unconnected-(X5-B-5-PadB5)") (class "Default")
      (node (ref "X5") (pin "B5") (pinfunction "B-5_B5") (pintype "passive"))
    )
    (net (code "118") (name "unconnected-(X5-B-6-PadB6)") (class "Default")
      (node (ref "X5") (pin "B6") (pinfunction "B-6_B6") (pintype "passive"))
    )
    (net (code "119") (name "unconnected-(X5-B-7-PadB7)") (class "Default")
      (node (ref "X5") (pin "B7") (pinfunction "B-7_B7") (pintype "passive"))
    )
    (net (code "120") (name "unconnected-(X5-B-8-PadB8)") (class "Default")
      (node (ref "X5") (pin "B8") (pinfunction "B-8_B8") (pintype "passive"))
    )
    (net (code "121") (name "unconnected-(X5-B-9-PadB9)") (class "Default")
      (node (ref "X5") (pin "B9") (pinfunction "B-9_B9") (pintype "passive"))
    )
    (net (code "122") (name "unconnected-(X5-B-10-PadB10)") (class "Default")
      (node (ref "X5") (pin "B10") (pinfunction "B-10_B10") (pintype "passive"))
    )
    (net (code "123") (name "unconnected-(X5-B-11-PadB11)") (class "Default")
      (node (ref "X5") (pin "B11") (pinfunction "B-11_B11") (pintype "passive"))
    )
    (net (code "124") (name "unconnected-(X5-B-12-PadB12)") (class "Default")
      (node (ref "X5") (pin "B12") (pinfunction "B-12_B12") (pintype "passive"))
    )
  )
)
